# pd.net
KiCad netlist of a schematic drawn in Altium Designer
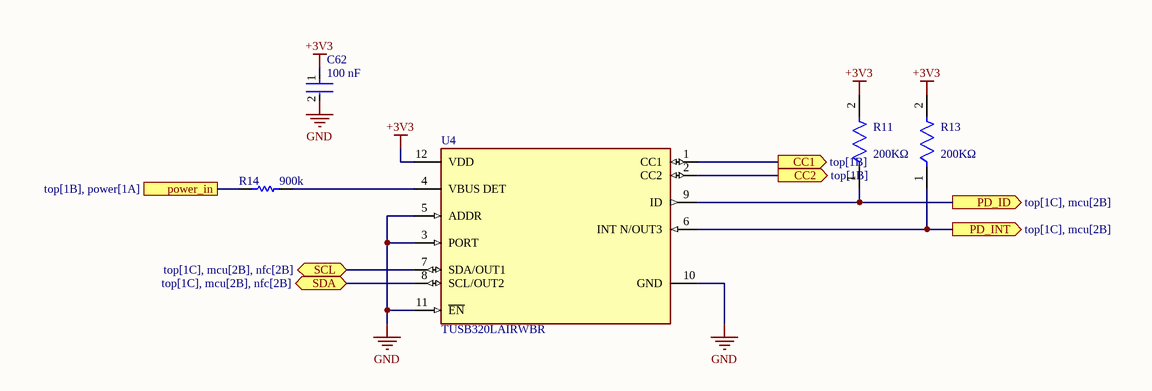
[diagram p0: pd.SchDoc]

(export (version "E")
  (design (tool "Eeschema 10.0.6"))
  (components
    (comp (ref "C62")
      (value "CC0603KRX7R7BB104")
      (footprint "FP-CC0603-DA-MFG")
      (description "CAP CER 0.1UF 16V X7R 0603")
      (fields
        (field (name "OCTOPART") "https://octopart.com/cc0603krx7r7bb104-yageo-192941")
        (field (name "TOLERANCE") "0.1")
        (field (name "CAPACITANCE") "100 nF")
      )
      (libsource (lib "Altium Content Vault") (part "11868f565c42a9108669ba33697ecf6"))
    )
    (comp (ref "R11")
      (value "200KΩ")
      (footprint "FP-RT0402-MFG")
      (description "RES SMD 200K OHM 0.1% 1/16W 0402")
      (fields (field (name "TOLERANCE") "0.001") (field (name "MANUFACTURER") "Yageo"))
      (libsource (lib "Altium Content Vault") (part "1029c3af85768c4190bb7ad29bc67b5"))
    )
    (comp (ref "R13")
      (value "200KΩ")
      (footprint "FP-RT0402-MFG")
      (description "RES SMD 200K OHM 0.1% 1/16W 0402")
      (fields (field (name "TOLERANCE") "0.001") (field (name "MANUFACTURER") "Yageo"))
      (libsource (lib "Altium Content Vault") (part "1029c3af85768c4190bb7ad29bc67b5"))
    )
    (comp (ref "R14")
      (value "900k")
      (footprint "RESC1005X40X25NL05T10")
      (fields (field (name "PART NUMBER") "RC0402FR-07910KL") (field (name "MANUFACTURER") "Yageo / Phycomp"))
      (libsource (lib "Altium Content Vault") (part "RES"))
    )
    (comp (ref "U4")
      (value "TUSB320LAIRWBR")
      (footprint "FP-RWB0012A-MFG")
      (description "IC USB TYPE-C LOGIC/PORT 12X2QFN")
      (libsource (lib "Altium Content Vault") (part "e586f20a714bee5deb71c786799b4c9"))
    )
  )
  (nets
    (net (code "1") (name "+3V3") (class "Default")
      (node (ref "C62") (pin "1") (pinfunction "1_1") (pintype "passive"))
      (node (ref "R11") (pin "2") (pinfunction "2_2") (pintype "passive"))
      (node (ref "R13") (pin "2") (pinfunction "2_2") (pintype "passive"))
      (node (ref "U4") (pin "12") (pinfunction "VDD_12") (pintype "power_in"))
    )
    (net (code "2") (name "/CC1") (class "Default")
      (node (ref "U4") (pin "1") (pinfunction "CC1_1") (pintype "bidirectional"))
    )
    (net (code "3") (name "/CC2") (class "Default")
      (node (ref "U4") (pin "2") (pinfunction "CC2_2") (pintype "bidirectional"))
    )
    (net (code "4") (name "/PD_ID") (class "Default")
      (node (ref "R11") (pin "1") (pinfunction "1_1") (pintype "passive"))
      (node (ref "U4") (pin "9") (pinfunction "ID_9") (pintype "output"))
    )
    (net (code "5") (name "/PD_INT") (class "Default")
      (node (ref "R13") (pin "1") (pinfunction "1_1") (pintype "passive"))
      (node (ref "U4") (pin "6") (pinfunction "INT_N/OUT3_6") (pintype "input"))
    )
    (net (code "6") (name "/SCL") (class "Default")
      (node (ref "U4") (pin "7") (pinfunction "SDA/OUT1_7") (pintype "bidirectional"))
    )
    (net (code "7") (name "/SDA") (class "Default")
      (node (ref "U4") (pin "8") (pinfunction "SCL/OUT2_8") (pintype "bidirectional"))
    )
    (net (code "8") (name "/power_in") (class "Default")
      (node (ref "R14") (pin "1") (pinfunction "1_1") (pintype "passive"))
    )
    (net (code "9") (name "GND") (class "Default")
      (node (ref "C62") (pin "2") (pinfunction "2_2") (pintype "passive"))
      (node (ref "U4") (pin "10") (pinfunction "GND_10") (pintype "power_in"))
      (node (ref "U4") (pin "11") (pinfunction "~{EN}_11") (pintype "input"))
      (node (ref "U4") (pin "3") (pinfunction "PORT_3") (pintype "input"))
      (node (ref "U4") (pin "5") (pinfunction "ADDR_5") (pintype "input"))
    )
    (net (code "10") (name "Net-(U4-VBUS_DET)") (class "Default")
      (node (ref "R14") (pin "2") (pinfunction "2_2") (pintype "passive"))
      (node (ref "U4") (pin "4") (pinfunction "VBUS_DET_4") (pintype "power_in"))
    )
  )
)
